# Adafruit_PowerBoost_1000_Basic.net
KiCad netlist of a schematic drawn in EAGLE
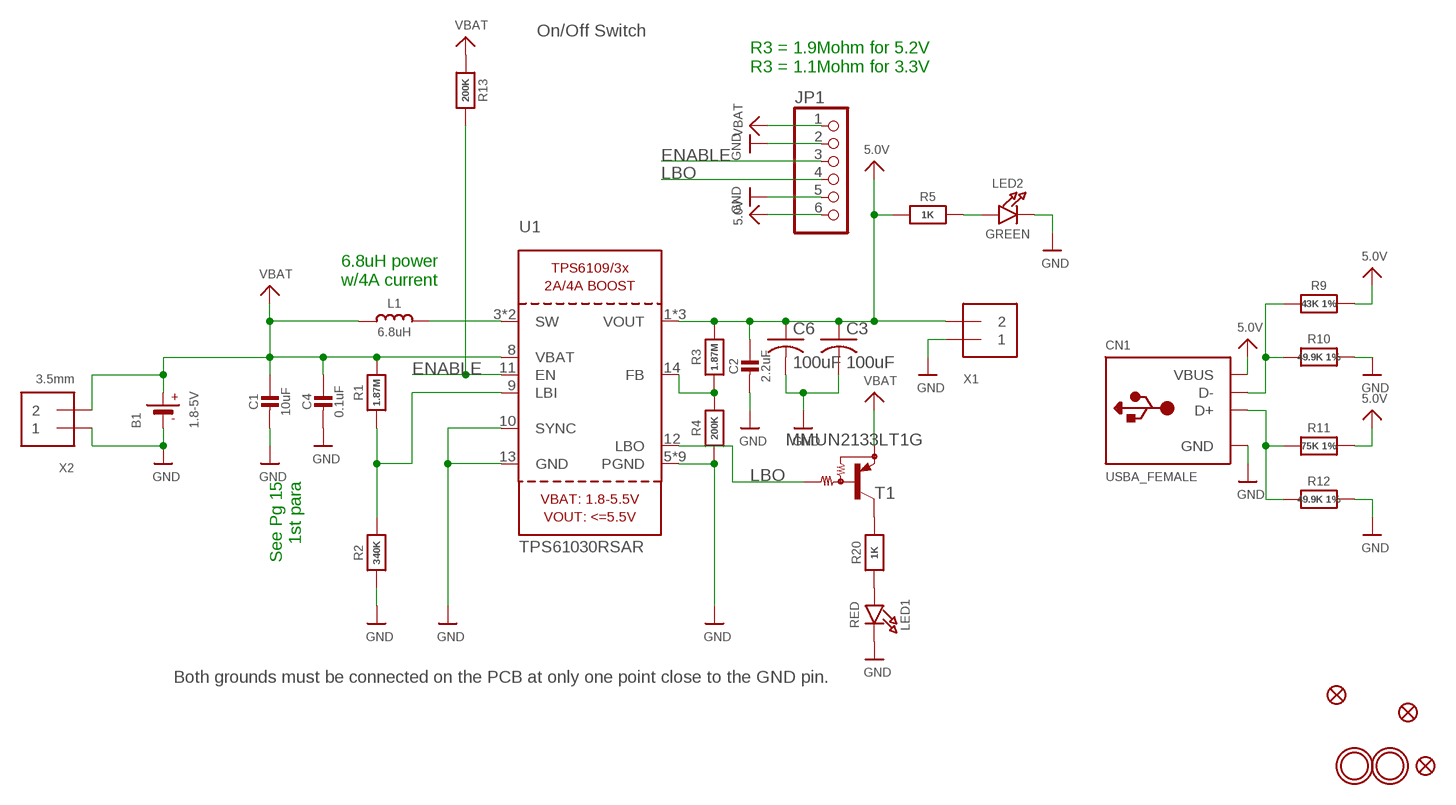
[diagram p0: schematic, sheet 1]

(export (version "E")
  (design (tool "Eeschema 10.0.6"))
  (components
    (comp (ref "B1")
      (value "1.8-5V")
      (footprint "eagle-import:JSTPH2")
      (libsource (lib "eagle-import") (part "BATTERY"))
    )
    (comp (ref "C1")
      (value "10uF")
      (footprint "eagle-import:0805-NO")
      (libsource (lib "eagle-import") (part "CAP_CERAMIC0805-NOOUTLINE"))
    )
    (comp (ref "C2")
      (value "2.2uF")
      (footprint "eagle-import:0805-NO")
      (libsource (lib "eagle-import") (part "CAP_CERAMIC0805-NOOUTLINE"))
    )
    (comp (ref "C3")
      (value "100uF")
      (footprint "eagle-import:C1210")
      (libsource (lib "eagle-import") (part "C-USC1210"))
    )
    (comp (ref "C4")
      (value "0.1uF")
      (footprint "eagle-import:0805-NO")
      (libsource (lib "eagle-import") (part "CAP_CERAMIC0805-NOOUTLINE"))
    )
    (comp (ref "C6")
      (value "100uF")
      (footprint "eagle-import:C1210")
      (libsource (lib "eagle-import") (part "C-USC1210"))
    )
    (comp (ref "CN1")
      (value "USBA_FEMALE")
      (footprint "eagle-import:USB_HOST-PTH")
      (libsource (lib "eagle-import") (part "USB_TYPEAPTHFML"))
    )
    (comp (ref "FID1")
      (value "FIDUCIAL\"\"")
      (footprint "eagle-import:FIDUCIAL_1MM")
      (fields (field (name "BOM") "EXCLUDE"))
      (libsource (lib "eagle-import") (part "FIDUCIAL{dblquote}{dblquote}"))
    )
    (comp (ref "FID2")
      (value "FIDUCIAL\"\"")
      (footprint "eagle-import:FIDUCIAL_1MM")
      (libsource (lib "eagle-import") (part "FIDUCIAL{dblquote}{dblquote}"))
    )
    (comp (ref "FID3")
      (value "FIDUCIAL\"\"")
      (footprint "eagle-import:FIDUCIAL_1MM")
      (fields (field (name "BOM") "EXCLUDE"))
      (libsource (lib "eagle-import") (part "FIDUCIAL{dblquote}{dblquote}"))
    )
    (comp (ref "JP1")
      (value "PINHD-1X6CB")
      (footprint "eagle-import:1X06-CLEANBIG")
      (libsource (lib "eagle-import") (part "PINHD-1X6CB"))
    )
    (comp (ref "L1")
      (value "6.8uH")
      (footprint "eagle-import:INDUCTOR_8X8MM")
      (libsource (lib "eagle-import") (part "INDUCTOR-8X8"))
    )
    (comp (ref "LED1")
      (value "RED")
      (footprint "eagle-import:CHIPLED_0805_NOOUTLINE")
      (libsource (lib "eagle-import") (part "LED0805_NOOUTLINE"))
    )
    (comp (ref "LED2")
      (value "GREEN")
      (footprint "eagle-import:CHIPLED_0805_NOOUTLINE")
      (libsource (lib "eagle-import") (part "LED0805_NOOUTLINE"))
    )
    (comp (ref "R1")
      (value "1.87M")
      (footprint "eagle-import:_0805MP")
      (libsource (lib "eagle-import") (part "RESISTOR_0805MP"))
    )
    (comp (ref "R2")
      (value "340K")
      (footprint "eagle-import:_0805MP")
      (libsource (lib "eagle-import") (part "RESISTOR_0805MP"))
    )
    (comp (ref "R3")
      (value "1.87M")
      (footprint "eagle-import:_0805MP")
      (libsource (lib "eagle-import") (part "RESISTOR_0805MP"))
    )
    (comp (ref "R4")
      (value "200K")
      (footprint "eagle-import:0805-NO")
      (libsource (lib "eagle-import") (part "RESISTOR0805_NOOUTLINE"))
    )
    (comp (ref "R5")
      (value "1K")
      (footprint "eagle-import:0805-NO")
      (libsource (lib "eagle-import") (part "RESISTOR0805_NOOUTLINE"))
    )
    (comp (ref "R9")
      (value "43K 1%")
      (footprint "eagle-import:0805-NO")
      (libsource (lib "eagle-import") (part "RESISTOR0805_NOOUTLINE"))
    )
    (comp (ref "R10")
      (value "49.9K 1%")
      (footprint "eagle-import:0805-NO")
      (libsource (lib "eagle-import") (part "RESISTOR0805_NOOUTLINE"))
    )
    (comp (ref "R11")
      (value "75K 1%")
      (footprint "eagle-import:0805-NO")
      (libsource (lib "eagle-import") (part "RESISTOR0805_NOOUTLINE"))
    )
    (comp (ref "R12")
      (value "49.9K 1%")
      (footprint "eagle-import:0805-NO")
      (libsource (lib "eagle-import") (part "RESISTOR0805_NOOUTLINE"))
    )
    (comp (ref "R13")
      (value "200K")
      (footprint "eagle-import:0805-NO")
      (libsource (lib "eagle-import") (part "RESISTOR0805_NOOUTLINE"))
    )
    (comp (ref "R20")
      (value "1K")
      (footprint "eagle-import:0805-NO")
      (libsource (lib "eagle-import") (part "RESISTOR0805_NOOUTLINE"))
    )
    (comp (ref "T1")
      (value "MMUN2133LT1G")
      (footprint "eagle-import:SC59-BEC")
      (libsource (lib "eagle-import") (part "-PNP_DRIVER-SC59-BECMUN2114T1"))
    )
    (comp (ref "U$10")
      (value "MOUNTINGHOLE2.5")
      (footprint "eagle-import:MOUNTINGHOLE_2.5_PLATED")
      (libsource (lib "eagle-import") (part "MOUNTINGHOLE2.5"))
    )
    (comp (ref "U$11")
      (value "MOUNTINGHOLE2.5")
      (footprint "eagle-import:MOUNTINGHOLE_2.5_PLATED")
      (libsource (lib "eagle-import") (part "MOUNTINGHOLE2.5"))
    )
    (comp (ref "U1")
      (value "TPS61030RSAR")
      (footprint "eagle-import:PVQFN-16")
      (libsource (lib "eagle-import") (part "VREG_TPS6103X"))
    )
    (comp (ref "X1")
      (value "TERMBLOCK_1X2")
      (footprint "eagle-import:TERMBLOCK_1X2-3.5MM")
      (libsource (lib "eagle-import") (part "TERMBLOCK_1X2"))
    )
    (comp (ref "X2")
      (value "3.5mm")
      (footprint "eagle-import:TERMBLOCK_1X2-3.5MM")
      (libsource (lib "eagle-import") (part "TERMBLOCK_1X2"))
    )
  )
  (nets
    (net (code "1") (name "/ENABLE") (class "Default")
      (node (ref "JP1") (pin "3") (pinfunction "3_3") (pintype "passive"))
      (node (ref "R13") (pin "2") (pinfunction "2_2") (pintype "passive"))
      (node (ref "U1") (pin "11") (pinfunction "EN_11") (pintype "input"))
    )
    (net (code "2") (name "/LBO") (class "Default")
      (node (ref "JP1") (pin "4") (pinfunction "4_4") (pintype "passive"))
      (node (ref "T1") (pin "B") (pinfunction "B_B") (pintype "passive"))
      (node (ref "U1") (pin "12") (pinfunction "LBO_12") (pintype "output"))
    )
    (net (code "3") (name "5.0V") (class "Default")
      (node (ref "C2") (pin "1") (pinfunction "1_1") (pintype "passive"))
      (node (ref "C3") (pin "1") (pinfunction "1_1") (pintype "passive"))
      (node (ref "C6") (pin "1") (pinfunction "1_1") (pintype "passive"))
      (node (ref "CN1") (pin "VBUS") (pinfunction "VBUS_VBUS") (pintype "power_in"))
      (node (ref "JP1") (pin "6") (pinfunction "6_6") (pintype "passive"))
      (node (ref "R11") (pin "2") (pinfunction "2_2") (pintype "passive"))
      (node (ref "R3") (pin "2") (pinfunction "2_2") (pintype "passive"))
      (node (ref "R5") (pin "1") (pinfunction "1_1") (pintype "passive"))
      (node (ref "R9") (pin "2") (pinfunction "2_2") (pintype "passive"))
      (node (ref "U1") (pin "1") (pinfunction "VOUT_1") (pintype "power_in"))
      (node (ref "U1") (pin "15") (pinfunction "VOUT_15") (pintype "power_in"))
      (node (ref "U1") (pin "16") (pinfunction "VOUT_16") (pintype "power_in"))
      (node (ref "X1") (pin "2") (pinfunction "2_2") (pintype "passive"))
    )
    (net (code "4") (name "GND") (class "Default")
      (node (ref "B1") (pin "1") (pinfunction "-_1") (pintype "passive"))
      (node (ref "C1") (pin "2") (pinfunction "2_2") (pintype "passive"))
      (node (ref "C2") (pin "2") (pinfunction "2_2") (pintype "passive"))
      (node (ref "C3") (pin "2") (pinfunction "2_2") (pintype "passive"))
      (node (ref "C4") (pin "2") (pinfunction "2_2") (pintype "passive"))
      (node (ref "C6") (pin "2") (pinfunction "2_2") (pintype "passive"))
      (node (ref "CN1") (pin "GND") (pinfunction "GND_GND") (pintype "power_in"))
      (node (ref "JP1") (pin "2") (pinfunction "2_2") (pintype "passive"))
      (node (ref "JP1") (pin "5") (pinfunction "5_5") (pintype "passive"))
      (node (ref "LED1") (pin "C") (pinfunction "C_C") (pintype "passive"))
      (node (ref "LED2") (pin "C") (pinfunction "C_C") (pintype "passive"))
      (node (ref "R10") (pin "2") (pinfunction "2_2") (pintype "passive"))
      (node (ref "R12") (pin "2") (pinfunction "2_2") (pintype "passive"))
      (node (ref "R2") (pin "1") (pinfunction "1_1") (pintype "passive"))
      (node (ref "R4") (pin "1") (pinfunction "1_1") (pintype "passive"))
      (node (ref "U1") (pin "10") (pinfunction "SYNC_10") (pintype "input"))
      (node (ref "U1") (pin "13") (pinfunction "GND_13") (pintype "power_in"))
      (node (ref "U1") (pin "5") (pinfunction "PGND_5") (pintype "power_in"))
      (node (ref "U1") (pin "6") (pinfunction "PGND_6") (pintype "power_in"))
      (node (ref "U1") (pin "7") (pinfunction "PGND_7") (pintype "power_in"))
      (node (ref "U1") (pin "P$18") (pinfunction "PGND_P$18") (pintype "power_in"))
      (node (ref "U1") (pin "P$19") (pinfunction "PGND_P$19") (pintype "power_in"))
      (node (ref "U1") (pin "P$20") (pinfunction "PGND_P$20") (pintype "power_in"))
      (node (ref "U1") (pin "P$21") (pinfunction "PGND_P$21") (pintype "power_in"))
      (node (ref "U1") (pin "P$22") (pinfunction "PGND_P$22") (pintype "power_in"))
      (node (ref "U1") (pin "THERMAL") (pinfunction "PGND_THERMAL") (pintype "power_in"))
      (node (ref "X1") (pin "1") (pinfunction "1_1") (pintype "passive"))
      (node (ref "X2") (pin "1") (pinfunction "1_1") (pintype "passive"))
    )
    (net (code "5") (name "Net-(CN1-PadD+)") (class "Default")
      (node (ref "CN1") (pin "D+") (pinfunction "D+_D+") (pintype "bidirectional"))
      (node (ref "R11") (pin "1") (pinfunction "1_1") (pintype "passive"))
      (node (ref "R12") (pin "1") (pinfunction "1_1") (pintype "passive"))
    )
    (net (code "6") (name "Net-(CN1-PadD-)") (class "Default")
      (node (ref "CN1") (pin "D-") (pinfunction "D-_D-") (pintype "bidirectional"))
      (node (ref "R10") (pin "1") (pinfunction "1_1") (pintype "passive"))
      (node (ref "R9") (pin "1") (pinfunction "1_1") (pintype "passive"))
    )
    (net (code "7") (name "Net-(L1-2)") (class "Default")
      (node (ref "L1") (pin "P$2") (pinfunction "2_P$2") (pintype "passive"))
      (node (ref "U1") (pin "3") (pinfunction "SW_3") (pintype "input"))
      (node (ref "U1") (pin "4") (pinfunction "SW_4") (pintype "input"))
    )
    (net (code "8") (name "Net-(LED1-PadA)") (class "Default")
      (node (ref "LED1") (pin "A") (pinfunction "A_A") (pintype "passive"))
      (node (ref "R20") (pin "1") (pinfunction "1_1") (pintype "passive"))
    )
    (net (code "9") (name "Net-(LED2-PadA)") (class "Default")
      (node (ref "LED2") (pin "A") (pinfunction "A_A") (pintype "passive"))
      (node (ref "R5") (pin "2") (pinfunction "2_2") (pintype "passive"))
    )
    (net (code "10") (name "Net-(R20-Pad2)") (class "Default")
      (node (ref "R20") (pin "2") (pinfunction "2_2") (pintype "passive"))
      (node (ref "T1") (pin "C") (pinfunction "C_C") (pintype "passive"))
    )
    (net (code "11") (name "Net-(U1-FB)") (class "Default")
      (node (ref "R3") (pin "1") (pinfunction "1_1") (pintype "passive"))
      (node (ref "R4") (pin "2") (pinfunction "2_2") (pintype "passive"))
      (node (ref "U1") (pin "14") (pinfunction "FB_14") (pintype "input"))
    )
    (net (code "12") (name "Net-(U1-LBI)") (class "Default")
      (node (ref "R1") (pin "1") (pinfunction "1_1") (pintype "passive"))
      (node (ref "R2") (pin "2") (pinfunction "2_2") (pintype "passive"))
      (node (ref "U1") (pin "9") (pinfunction "LBI_9") (pintype "input"))
    )
    (net (code "13") (name "VBAT") (class "Default")
      (node (ref "B1") (pin "2") (pinfunction "+_2") (pintype "passive"))
      (node (ref "C1") (pin "1") (pinfunction "1_1") (pintype "passive"))
      (node (ref "C4") (pin "1") (pinfunction "1_1") (pintype "passive"))
      (node (ref "JP1") (pin "1") (pinfunction "1_1") (pintype "passive"))
      (node (ref "L1") (pin "P$1") (pinfunction "1_P$1") (pintype "passive"))
      (node (ref "R1") (pin "2") (pinfunction "2_2") (pintype "passive"))
      (node (ref "R13") (pin "1") (pinfunction "1_1") (pintype "passive"))
      (node (ref "T1") (pin "E") (pinfunction "E_E") (pintype "passive"))
      (node (ref "U1") (pin "8") (pinfunction "VBAT_8") (pintype "input"))
      (node (ref "X2") (pin "2") (pinfunction "2_2") (pintype "passive"))
    )
  )
)
